# Power.net
KiCad netlist of a schematic drawn in Altium Designer
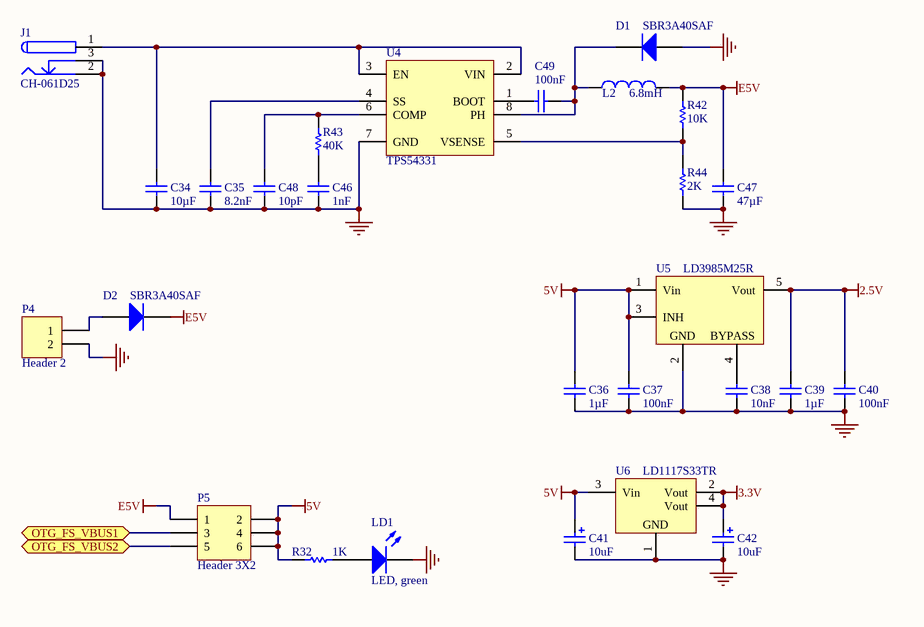
[diagram p0: Power.SchDoc]

(export (version "E")
  (design (tool "Eeschema 10.0.6"))
  (components
    (comp (ref "C34")
      (value "10µF")
      (footprint "CAPC3216N")
      (description "Capacitor")
      (fields (field (name "Comment") "Cap"))
      (libsource (lib "Core429IBaseBoard") (part "Cap"))
    )
    (comp (ref "C35")
      (value "8.2nF")
      (footprint "CAPC2012N")
      (description "Capacitor")
      (fields (field (name "Comment") "Cap"))
      (libsource (lib "Core429IBaseBoard") (part "Cap"))
    )
    (comp (ref "C36")
      (value "1µF")
      (footprint "CAPC3216N")
      (description "Capacitor")
      (fields (field (name "Comment") "Cap"))
      (libsource (lib "Core429IBaseBoard") (part "Cap"))
    )
    (comp (ref "C37")
      (value "100nF")
      (footprint "CAPC2012N")
      (description "Capacitor")
      (fields (field (name "Comment") "Cap"))
      (libsource (lib "Core429IBaseBoard") (part "Cap"))
    )
    (comp (ref "C38")
      (value "10nF")
      (footprint "CAPC2012N")
      (description "Capacitor")
      (fields (field (name "Comment") "Cap"))
      (libsource (lib "Core429IBaseBoard") (part "Cap"))
    )
    (comp (ref "C39")
      (value "1µF")
      (footprint "CAPC3216N")
      (description "Capacitor")
      (fields (field (name "Comment") "Cap"))
      (libsource (lib "Core429IBaseBoard") (part "Cap"))
    )
    (comp (ref "C40")
      (value "100nF")
      (footprint "CAPC2012N")
      (description "Capacitor")
      (fields (field (name "Comment") "Cap"))
      (libsource (lib "Core429IBaseBoard") (part "Cap"))
    )
    (comp (ref "C41")
      (value "10uF")
      (footprint "TC3216-1206")
      (description "Polarized Capacitor")
      (fields (field (name "Comment") "Cap Pol"))
      (libsource (lib "Core429IBaseBoard") (part "Cap Pol"))
    )
    (comp (ref "C42")
      (value "10uF")
      (footprint "TC3216-1206")
      (description "Polarized Capacitor")
      (fields (field (name "Comment") "Cap Pol"))
      (libsource (lib "Core429IBaseBoard") (part "Cap Pol"))
    )
    (comp (ref "C46")
      (value "1nF")
      (footprint "CAPC2012N")
      (description "Capacitor")
      (fields (field (name "Comment") "Cap"))
      (libsource (lib "Core429IBaseBoard") (part "Cap"))
    )
    (comp (ref "C47")
      (value "47µF")
      (footprint "CAPC3216N")
      (description "Capacitor")
      (fields (field (name "Comment") "Cap"))
      (libsource (lib "Core429IBaseBoard") (part "Cap"))
    )
    (comp (ref "C48")
      (value "10pF")
      (footprint "CAPC2012N")
      (description "Capacitor")
      (fields (field (name "Comment") "Cap"))
      (libsource (lib "Core429IBaseBoard") (part "Cap"))
    )
    (comp (ref "C49")
      (value "100nF")
      (footprint "CAPC2012N")
      (description "Capacitor")
      (fields (field (name "Comment") "Cap"))
      (libsource (lib "Core429IBaseBoard") (part "Cap"))
    )
    (comp (ref "D1")
      (value "SBR3A40SAF")
      (footprint "CD-DO214AC")
      (description "Default Diode")
      (libsource (lib "Core429IBaseBoardVerE") (part "Diode"))
    )
    (comp (ref "D2")
      (value "SBR3A40SAF")
      (footprint "CD-DO214AC")
      (description "Default Diode")
      (libsource (lib "Core429IBaseBoardVerE") (part "Diode"))
    )
    (comp (ref "J1")
      (value "CH-061D25")
      (footprint "CH-061D25")
      (description "Low Voltage Power Supply Connector")
      (libsource (lib "Core429IBaseBoard") (part "PWR2.5"))
    )
    (comp (ref "L2")
      (value "6.8mH")
      (footprint "INDP6560X45M")
      (description "Inductor")
      (libsource (lib "Core429IBaseBoardVerF") (part "Inductor"))
    )
    (comp (ref "LD1")
      (value "LED, green")
      (footprint "CLED2012-0805")
      (description "Light emitting diode")
      (libsource (lib "Core429IBaseBoard") (part "LED"))
    )
    (comp (ref "P4")
      (value "Header 2")
      (footprint "HDR1X2H")
      (description "Header, 2-Pin")
      (libsource (lib "Core429IBaseBoardVerE") (part "Header 2"))
    )
    (comp (ref "P5")
      (value "Header 3X2")
      (footprint "HDR2X3")
      (description "Header, 3-Pin, Dual row")
      (libsource (lib "Core429IBaseBoardVerE") (part "Header 3X2"))
    )
    (comp (ref "R32")
      (value "1K")
      (footprint "RESC2012N")
      (description "Resistor")
      (fields (field (name "Comment") "1206"))
      (libsource (lib "Core429IBaseBoard") (part "Res"))
    )
    (comp (ref "R42")
      (value "10K")
      (footprint "RESC2012N")
      (description "Resistor")
      (fields (field (name "Comment") "Res"))
      (libsource (lib "Core429IBaseBoardVerF") (part "Res"))
    )
    (comp (ref "R43")
      (value "40K")
      (footprint "RESC2012N")
      (description "Resistor")
      (fields (field (name "Comment") "Res"))
      (libsource (lib "Core429IBaseBoardVerF") (part "Res"))
    )
    (comp (ref "R44")
      (value "2K")
      (footprint "RESC2012N")
      (description "Resistor")
      (fields (field (name "Comment") "Res"))
      (libsource (lib "Core429IBaseBoardVerF") (part "Res"))
    )
    (comp (ref "U4")
      (value "TPS54331")
      (footprint "SOIC127P600X173-8M")
      (description "3-A, 28-V Input, Step Down DC-DC Converter With Eco-mode")
      (libsource (lib "Core429IBaseBoardVerF") (part "TPS54331"))
    )
    (comp (ref "U5")
      (value "LD3985M25R")
      (footprint "SOT95P280X145-5M")
      (description "Ultra low drop-low noise BiCMOS voltage  regulators low ESR capacitors compatible")
      (libsource (lib "Core429IBaseBoard") (part "LD3985M"))
    )
    (comp (ref "U6")
      (value "LD1117S33TR")
      (footprint "SOT230P700X181-4M")
      (description "Adjustable and fixed low drop positive voltage regulator")
      (libsource (lib "Core429IBaseBoard") (part "LD1117S"))
    )
  )
  (nets
    (net (code "1") (name "/OTG_FS_VBUS1") (class "Default")
      (node (ref "P5") (pin "3") (pinfunction "3_3") (pintype "passive"))
    )
    (net (code "2") (name "/OTG_FS_VBUS2") (class "Default")
      (node (ref "P5") (pin "5") (pinfunction "5_5") (pintype "passive"))
    )
    (net (code "3") (name "2.5V") (class "Default")
      (node (ref "C39") (pin "2") (pinfunction "2_2") (pintype "passive"))
      (node (ref "C40") (pin "2") (pinfunction "2_2") (pintype "passive"))
      (node (ref "U5") (pin "5") (pinfunction "Vout_5") (pintype "passive"))
    )
    (net (code "4") (name "3.3V") (class "Default")
      (node (ref "C42") (pin "1") (pinfunction "1_1") (pintype "passive"))
      (node (ref "U6") (pin "2") (pinfunction "Vout_2") (pintype "passive"))
      (node (ref "U6") (pin "4") (pinfunction "Vout_4") (pintype "passive"))
    )
    (net (code "5") (name "5V") (class "Default")
      (node (ref "C36") (pin "2") (pinfunction "2_2") (pintype "passive"))
      (node (ref "C37") (pin "2") (pinfunction "2_2") (pintype "passive"))
      (node (ref "C41") (pin "1") (pinfunction "1_1") (pintype "passive"))
      (node (ref "P5") (pin "2") (pinfunction "2_2") (pintype "passive"))
      (node (ref "P5") (pin "4") (pinfunction "4_4") (pintype "passive"))
      (node (ref "P5") (pin "6") (pinfunction "6_6") (pintype "passive"))
      (node (ref "R32") (pin "2") (pinfunction "2_2") (pintype "passive"))
      (node (ref "U5") (pin "1") (pinfunction "Vin_1") (pintype "passive"))
      (node (ref "U5") (pin "3") (pinfunction "INH_3") (pintype "passive"))
      (node (ref "U6") (pin "3") (pinfunction "Vin_3") (pintype "passive"))
    )
    (net (code "6") (name "DGND") (class "Default")
      (node (ref "C34") (pin "1") (pinfunction "1_1") (pintype "passive"))
      (node (ref "C35") (pin "1") (pinfunction "1_1") (pintype "passive"))
      (node (ref "C36") (pin "1") (pinfunction "1_1") (pintype "passive"))
      (node (ref "C37") (pin "1") (pinfunction "1_1") (pintype "passive"))
      (node (ref "C38") (pin "1") (pinfunction "1_1") (pintype "passive"))
      (node (ref "C39") (pin "1") (pinfunction "1_1") (pintype "passive"))
      (node (ref "C40") (pin "1") (pinfunction "1_1") (pintype "passive"))
      (node (ref "C41") (pin "2") (pinfunction "2_2") (pintype "passive"))
      (node (ref "C42") (pin "2") (pinfunction "2_2") (pintype "passive"))
      (node (ref "C46") (pin "1") (pinfunction "1_1") (pintype "passive"))
      (node (ref "C47") (pin "1") (pinfunction "1_1") (pintype "passive"))
      (node (ref "C48") (pin "1") (pinfunction "1_1") (pintype "passive"))
      (node (ref "D1") (pin "1") (pinfunction "A_1") (pintype "passive"))
      (node (ref "J1") (pin "2") (pintype "passive"))
      (node (ref "J1") (pin "3") (pintype "passive"))
      (node (ref "LD1") (pin "2") (pinfunction "K_2") (pintype "passive"))
      (node (ref "P4") (pin "2") (pinfunction "2_2") (pintype "passive"))
      (node (ref "R44") (pin "1") (pinfunction "1_1") (pintype "passive"))
      (node (ref "U4") (pin "7") (pinfunction "GND_7") (pintype "passive"))
      (node (ref "U5") (pin "2") (pinfunction "GND_2") (pintype "passive"))
      (node (ref "U6") (pin "1") (pinfunction "GND_1") (pintype "passive"))
    )
    (net (code "7") (name "E5V") (class "Default")
      (node (ref "C47") (pin "2") (pinfunction "2_2") (pintype "passive"))
      (node (ref "D2") (pin "2") (pinfunction "K_2") (pintype "passive"))
      (node (ref "L2") (pin "2") (pinfunction "2_2") (pintype "passive"))
      (node (ref "P5") (pin "1") (pinfunction "1_1") (pintype "passive"))
      (node (ref "R42") (pin "2") (pinfunction "2_2") (pintype "passive"))
    )
    (net (code "8") (name "Net-(C46-Pad2)") (class "Default")
      (node (ref "C46") (pin "2") (pinfunction "2_2") (pintype "passive"))
      (node (ref "R43") (pin "1") (pinfunction "1_1") (pintype "passive"))
    )
    (net (code "9") (name "Net-(D1-K)") (class "Default")
      (node (ref "C49") (pin "1") (pinfunction "1_1") (pintype "passive"))
      (node (ref "D1") (pin "2") (pinfunction "K_2") (pintype "passive"))
      (node (ref "L2") (pin "1") (pinfunction "1_1") (pintype "passive"))
      (node (ref "U4") (pin "8") (pinfunction "PH_8") (pintype "passive"))
    )
    (net (code "10") (name "Net-(D2-A)") (class "Default")
      (node (ref "D2") (pin "1") (pinfunction "A_1") (pintype "passive"))
      (node (ref "P4") (pin "1") (pinfunction "1_1") (pintype "passive"))
    )
    (net (code "11") (name "Net-(LD1-A)") (class "Default")
      (node (ref "LD1") (pin "1") (pinfunction "A_1") (pintype "passive"))
      (node (ref "R32") (pin "1") (pinfunction "1_1") (pintype "passive"))
    )
    (net (code "12") (name "Net-(U4-BOOT)") (class "Default")
      (node (ref "C49") (pin "2") (pinfunction "2_2") (pintype "passive"))
      (node (ref "U4") (pin "1") (pinfunction "BOOT_1") (pintype "passive"))
    )
    (net (code "13") (name "Net-(U4-COMP)") (class "Default")
      (node (ref "C48") (pin "2") (pinfunction "2_2") (pintype "passive"))
      (node (ref "R43") (pin "2") (pinfunction "2_2") (pintype "passive"))
      (node (ref "U4") (pin "6") (pinfunction "COMP_6") (pintype "passive"))
    )
    (net (code "14") (name "Net-(U4-EN)") (class "Default")
      (node (ref "C34") (pin "2") (pinfunction "2_2") (pintype "passive"))
      (node (ref "J1") (pin "1") (pintype "passive"))
      (node (ref "U4") (pin "2") (pinfunction "VIN_2") (pintype "passive"))
      (node (ref "U4") (pin "3") (pinfunction "EN_3") (pintype "passive"))
    )
    (net (code "15") (name "Net-(U4-SS)") (class "Default")
      (node (ref "C35") (pin "2") (pinfunction "2_2") (pintype "passive"))
      (node (ref "U4") (pin "4") (pinfunction "SS_4") (pintype "passive"))
    )
    (net (code "16") (name "Net-(U4-VSENSE)") (class "Default")
      (node (ref "R42") (pin "1") (pinfunction "1_1") (pintype "passive"))
      (node (ref "R44") (pin "2") (pinfunction "2_2") (pintype "passive"))
      (node (ref "U4") (pin "5") (pinfunction "VSENSE_5") (pintype "passive"))
    )
    (net (code "17") (name "Net-(U5-BYPASS)") (class "Default")
      (node (ref "C38") (pin "2") (pinfunction "2_2") (pintype "passive"))
      (node (ref "U5") (pin "4") (pinfunction "BYPASS_4") (pintype "passive"))
    )
  )
)
